# voltage_sensor_v0_3.net
KiCad netlist of a schematic drawn in EAGLE
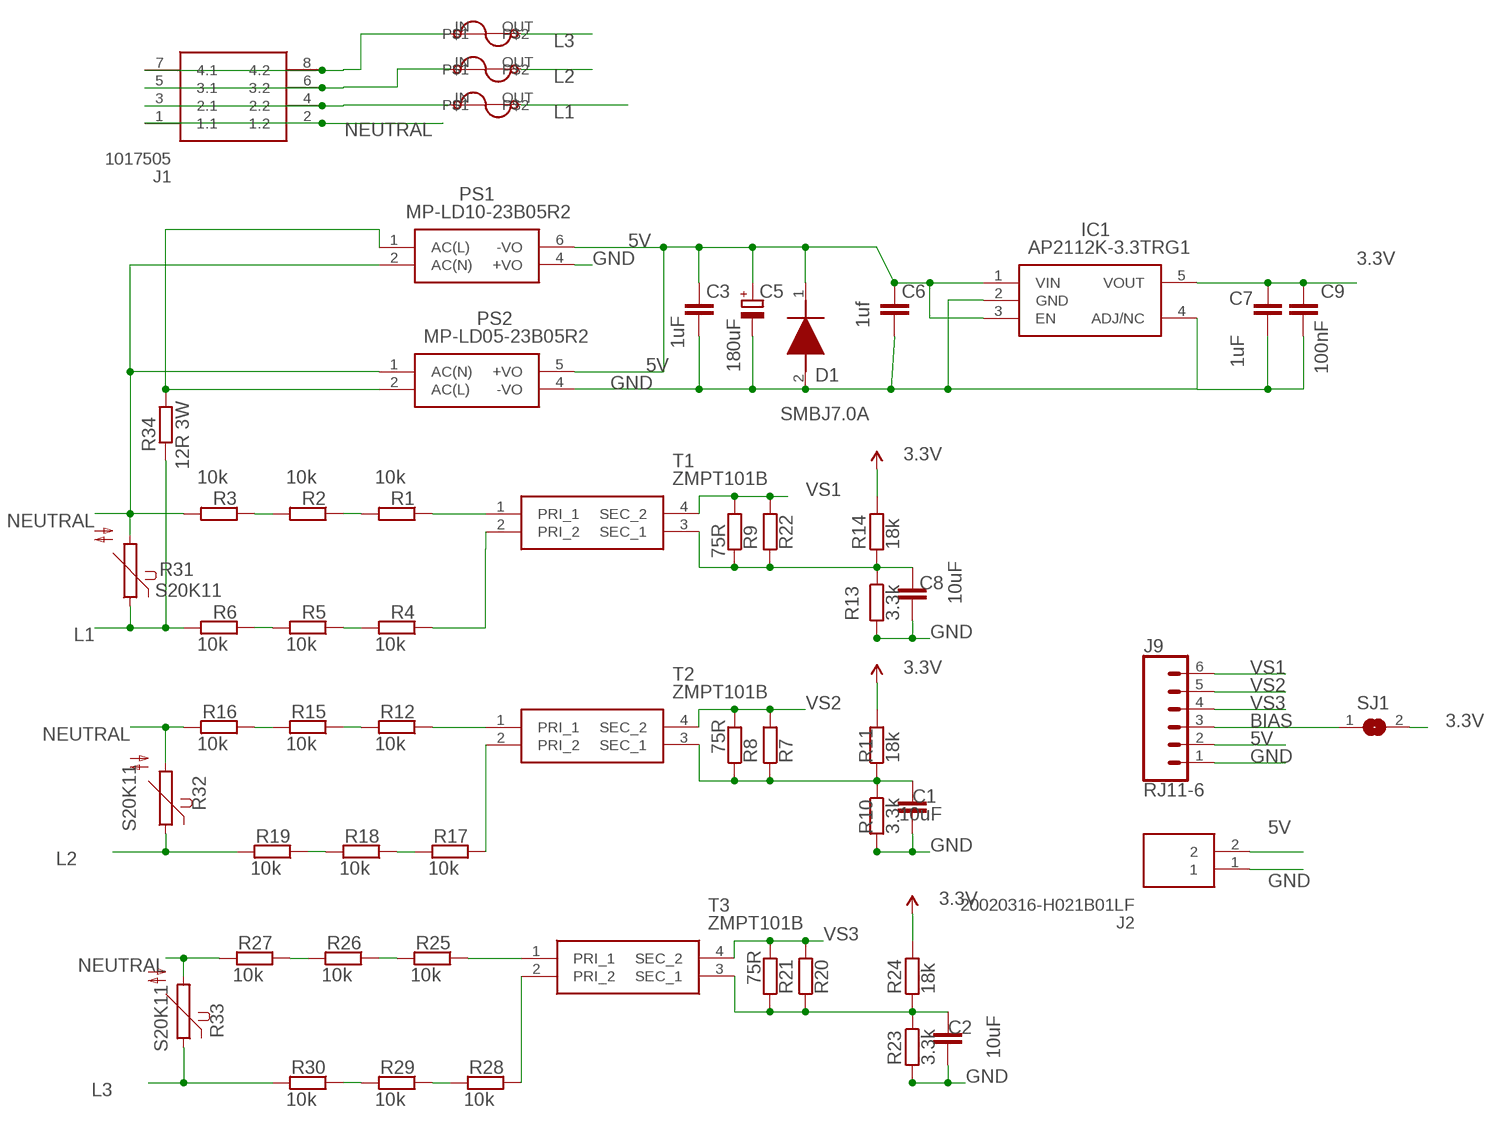
[diagram p0: schematic, sheet 1]

(export (version "E")
  (design (tool "Eeschema 10.0.6"))
  (components
    (comp (ref "C1")
      (value "10uF")
      (footprint "eagle-import:C0603")
      (libsource (lib "eagle-import") (part "C-EUC0603"))
    )
    (comp (ref "C2")
      (value "10uF")
      (footprint "eagle-import:C0603")
      (libsource (lib "eagle-import") (part "C-EUC0603"))
    )
    (comp (ref "C3")
      (value "1uF")
      (footprint "eagle-import:C0603")
      (libsource (lib "eagle-import") (part "C-EUC0603"))
    )
    (comp (ref "C5")
      (value "180uF")
      (footprint "eagle-import:PANASONIC_C")
      (libsource (lib "eagle-import") (part "CPOL-EUC"))
    )
    (comp (ref "C6")
      (value "1uf")
      (footprint "eagle-import:C0603")
      (libsource (lib "eagle-import") (part "C-EUC0603"))
    )
    (comp (ref "C7")
      (value "1uF")
      (footprint "eagle-import:C0603")
      (libsource (lib "eagle-import") (part "C-EUC0603"))
    )
    (comp (ref "C8")
      (value "10uF")
      (footprint "eagle-import:C0603")
      (libsource (lib "eagle-import") (part "C-EUC0603"))
    )
    (comp (ref "C9")
      (value "100nF")
      (footprint "eagle-import:C0603")
      (libsource (lib "eagle-import") (part "C-EUC0603"))
    )
    (comp (ref "D1")
      (value "SMBJ7.0A")
      (footprint "eagle-import:DIOM5336X244N")
      (libsource (lib "eagle-import") (part "SMBJ7.0A"))
    )
    (comp (ref "F1")
      (value "2A/250V")
      (footprint "eagle-import:BELFUSE1A")
      (libsource (lib "eagle-import") (part "BEL1AFUSE"))
    )
    (comp (ref "F2")
      (value "2A/250V")
      (footprint "eagle-import:BELFUSE1A")
      (libsource (lib "eagle-import") (part "BEL1AFUSE"))
    )
    (comp (ref "F3")
      (value "2A/250V")
      (footprint "eagle-import:BELFUSE1A")
      (libsource (lib "eagle-import") (part "BEL1AFUSE"))
    )
    (comp (ref "IC1")
      (value "AP2112K-3.3TRG1")
      (footprint "eagle-import:SOT95P282X130-5N")
      (fields (field (name "MOUSER_PART_NUMBER") "621-AP2112K-3.3TRG1"))
      (libsource (lib "eagle-import") (part "AP2112K-3.3TRG1"))
    )
    (comp (ref "J1")
      (value "1017505")
      (footprint "eagle-import:1017505")
      (fields (field (name "MOUSER_PART_NUMBER") "651-1017505"))
      (libsource (lib "eagle-import") (part "1017505"))
    )
    (comp (ref "J2")
      (value "20020316-H021B01LF")
      (footprint "eagle-import:20020316H021B01LF")
      (libsource (lib "eagle-import") (part "20020316-H021B01LF"))
    )
    (comp (ref "J9")
      (value "RJ11-6")
      (footprint "eagle-import:RJ11-6")
      (libsource (lib "eagle-import") (part "RJ11-6"))
    )
    (comp (ref "PS1")
      (value "MP-LD10-23B05R2")
      (footprint "eagle-import:MPLD1023B12R2")
      (libsource (lib "eagle-import") (part "MP-LD10-23B12R2"))
    )
    (comp (ref "PS2")
      (value "MP-LD05-23B05R2")
      (footprint "eagle-import:MPLD0523B03R2")
      (fields (field (name "MANUFACTURER_PART_NUMBER") "MP-LD05-23B03R2"))
      (libsource (lib "eagle-import") (part "MP-LD05-23B03R2"))
    )
    (comp (ref "R1")
      (value "10k")
      (footprint "eagle-import:R0603")
      (libsource (lib "eagle-import") (part "R-EU_R0603"))
    )
    (comp (ref "R2")
      (value "10k")
      (footprint "eagle-import:R0603")
      (libsource (lib "eagle-import") (part "R-EU_R0603"))
    )
    (comp (ref "R3")
      (value "10k")
      (footprint "eagle-import:R0603")
      (libsource (lib "eagle-import") (part "R-EU_R0603"))
    )
    (comp (ref "R4")
      (value "10k")
      (footprint "eagle-import:R0603")
      (libsource (lib "eagle-import") (part "R-EU_R0603"))
    )
    (comp (ref "R5")
      (value "10k")
      (footprint "eagle-import:R0603")
      (libsource (lib "eagle-import") (part "R-EU_R0603"))
    )
    (comp (ref "R6")
      (value "10k")
      (footprint "eagle-import:R0603")
      (libsource (lib "eagle-import") (part "R-EU_R0603"))
    )
    (comp (ref "R7")
      (value "R-EU_0204/7")
      (footprint "eagle-import:0204_7")
      (libsource (lib "eagle-import") (part "R-EU_0204/7"))
    )
    (comp (ref "R8")
      (value "75R")
      (footprint "eagle-import:R0603")
      (libsource (lib "eagle-import") (part "R-EU_R0603"))
    )
    (comp (ref "R9")
      (value "75R")
      (footprint "eagle-import:R0603")
      (libsource (lib "eagle-import") (part "R-EU_R0603"))
    )
    (comp (ref "R10")
      (value "3.3k")
      (footprint "eagle-import:R0603")
      (libsource (lib "eagle-import") (part "R-EU_R0603"))
    )
    (comp (ref "R11")
      (value "18k")
      (footprint "eagle-import:R0603")
      (libsource (lib "eagle-import") (part "R-EU_R0603"))
    )
    (comp (ref "R12")
      (value "10k")
      (footprint "eagle-import:R0603")
      (libsource (lib "eagle-import") (part "R-EU_R0603"))
    )
    (comp (ref "R13")
      (value "3.3k")
      (footprint "eagle-import:R0603")
      (libsource (lib "eagle-import") (part "R-EU_R0603"))
    )
    (comp (ref "R14")
      (value "18k")
      (footprint "eagle-import:R0603")
      (libsource (lib "eagle-import") (part "R-EU_R0603"))
    )
    (comp (ref "R15")
      (value "10k")
      (footprint "eagle-import:R0603")
      (libsource (lib "eagle-import") (part "R-EU_R0603"))
    )
    (comp (ref "R16")
      (value "10k")
      (footprint "eagle-import:R0603")
      (libsource (lib "eagle-import") (part "R-EU_R0603"))
    )
    (comp (ref "R17")
      (value "10k")
      (footprint "eagle-import:R0603")
      (libsource (lib "eagle-import") (part "R-EU_R0603"))
    )
    (comp (ref "R18")
      (value "10k")
      (footprint "eagle-import:R0603")
      (libsource (lib "eagle-import") (part "R-EU_R0603"))
    )
    (comp (ref "R19")
      (value "10k")
      (footprint "eagle-import:R0603")
      (libsource (lib "eagle-import") (part "R-EU_R0603"))
    )
    (comp (ref "R20")
      (value "R-EU_0204/7")
      (footprint "eagle-import:0204_7")
      (libsource (lib "eagle-import") (part "R-EU_0204/7"))
    )
    (comp (ref "R21")
      (value "75R")
      (footprint "eagle-import:R0603")
      (libsource (lib "eagle-import") (part "R-EU_R0603"))
    )
    (comp (ref "R22")
      (value "R-EU_0204/7")
      (footprint "eagle-import:0204_7")
      (libsource (lib "eagle-import") (part "R-EU_0204/7"))
    )
    (comp (ref "R23")
      (value "3.3k")
      (footprint "eagle-import:R0603")
      (libsource (lib "eagle-import") (part "R-EU_R0603"))
    )
    (comp (ref "R24")
      (value "18k")
      (footprint "eagle-import:R0603")
      (libsource (lib "eagle-import") (part "R-EU_R0603"))
    )
    (comp (ref "R25")
      (value "10k")
      (footprint "eagle-import:R0603")
      (libsource (lib "eagle-import") (part "R-EU_R0603"))
    )
    (comp (ref "R26")
      (value "10k")
      (footprint "eagle-import:R0603")
      (libsource (lib "eagle-import") (part "R-EU_R0603"))
    )
    (comp (ref "R27")
      (value "10k")
      (footprint "eagle-import:R0603")
      (libsource (lib "eagle-import") (part "R-EU_R0603"))
    )
    (comp (ref "R28")
      (value "10k")
      (footprint "eagle-import:R0603")
      (libsource (lib "eagle-import") (part "R-EU_R0603"))
    )
    (comp (ref "R29")
      (value "10k")
      (footprint "eagle-import:R0603")
      (libsource (lib "eagle-import") (part "R-EU_R0603"))
    )
    (comp (ref "R30")
      (value "10k")
      (footprint "eagle-import:R0603")
      (libsource (lib "eagle-import") (part "R-EU_R0603"))
    )
    (comp (ref "R31")
      (value "S20K11")
      (footprint "eagle-import:S20K11")
      (libsource (lib "eagle-import") (part "S20K11"))
    )
    (comp (ref "R32")
      (value "S20K11")
      (footprint "eagle-import:S20K11")
      (libsource (lib "eagle-import") (part "S20K11"))
    )
    (comp (ref "R33")
      (value "S20K11")
      (footprint "eagle-import:S20K11")
      (libsource (lib "eagle-import") (part "S20K11"))
    )
    (comp (ref "R34")
      (value "12R 3W")
      (footprint "eagle-import:R2512")
      (libsource (lib "eagle-import") (part "rcl_334_R-EU_R2512"))
    )
    (comp (ref "SJ1") (value "SJ") (footprint "eagle-import:SJ") (libsource (lib "eagle-import") (part "SJ")))
    (comp (ref "T1")
      (value "ZMPT101B")
      (footprint "eagle-import:ZMPT101B")
      (libsource (lib "eagle-import") (part "ZMPT101B"))
    )
    (comp (ref "T2")
      (value "ZMPT101B")
      (footprint "eagle-import:ZMPT101B")
      (libsource (lib "eagle-import") (part "ZMPT101B"))
    )
    (comp (ref "T3")
      (value "ZMPT101B")
      (footprint "eagle-import:ZMPT101B")
      (libsource (lib "eagle-import") (part "ZMPT101B"))
    )
  )
  (nets
    (net (code "1") (name "/5V") (class "Default")
      (node (ref "C3") (pin "1") (pinfunction "1_1") (pintype "passive"))
      (node (ref "C5") (pin "+") (pinfunction "+_+") (pintype "passive"))
      (node (ref "C6") (pin "1") (pinfunction "1_1") (pintype "passive"))
      (node (ref "D1") (pin "1") (pinfunction "K_1") (pintype "bidirectional"))
      (node (ref "IC1") (pin "1") (pinfunction "VIN_1") (pintype "bidirectional"))
      (node (ref "IC1") (pin "3") (pinfunction "EN_3") (pintype "bidirectional"))
      (node (ref "J2") (pin "2") (pinfunction "2_2") (pintype "bidirectional"))
      (node (ref "J9") (pin "2") (pinfunction "2_2") (pintype "passive"))
      (node (ref "PS1") (pin "6") (pinfunction "-VO_6") (pintype "bidirectional"))
      (node (ref "PS2") (pin "5") (pinfunction "+VO_5") (pintype "bidirectional"))
    )
    (net (code "2") (name "/BIAS") (class "Default")
      (node (ref "J9") (pin "3") (pinfunction "3_3") (pintype "passive"))
      (node (ref "SJ1") (pin "1") (pinfunction "1_1") (pintype "passive"))
    )
    (net (code "3") (name "/GND") (class "Default")
      (node (ref "C1") (pin "2") (pinfunction "2_2") (pintype "passive"))
      (node (ref "C2") (pin "2") (pinfunction "2_2") (pintype "passive"))
      (node (ref "C3") (pin "2") (pinfunction "2_2") (pintype "passive"))
      (node (ref "C5") (pin "-") (pinfunction "-_-") (pintype "passive"))
      (node (ref "C6") (pin "2") (pinfunction "2_2") (pintype "passive"))
      (node (ref "C7") (pin "2") (pinfunction "2_2") (pintype "passive"))
      (node (ref "C8") (pin "2") (pinfunction "2_2") (pintype "passive"))
      (node (ref "C9") (pin "2") (pinfunction "2_2") (pintype "passive"))
      (node (ref "D1") (pin "2") (pinfunction "A_2") (pintype "bidirectional"))
      (node (ref "IC1") (pin "2") (pinfunction "GND_2") (pintype "bidirectional"))
      (node (ref "IC1") (pin "4") (pinfunction "ADJ/NC_4") (pintype "bidirectional"))
      (node (ref "J2") (pin "1") (pinfunction "1_1") (pintype "bidirectional"))
      (node (ref "J9") (pin "1") (pinfunction "1_1") (pintype "passive"))
      (node (ref "PS1") (pin "4") (pinfunction "+VO_4") (pintype "bidirectional"))
      (node (ref "PS2") (pin "4") (pinfunction "-VO_4") (pintype "bidirectional"))
      (node (ref "R10") (pin "2") (pinfunction "2_2") (pintype "passive"))
      (node (ref "R13") (pin "2") (pinfunction "2_2") (pintype "passive"))
      (node (ref "R23") (pin "2") (pinfunction "2_2") (pintype "passive"))
    )
    (net (code "4") (name "/L1") (class "Default")
      (node (ref "F1") (pin "OUT") (pinfunction "P$1_OUT") (pintype "bidirectional"))
      (node (ref "R31") (pin "1") (pinfunction "1_1") (pintype "passive"))
      (node (ref "R34") (pin "1") (pinfunction "1_1") (pintype "passive"))
      (node (ref "R6") (pin "2") (pinfunction "2_2") (pintype "passive"))
    )
    (net (code "5") (name "/L2") (class "Default")
      (node (ref "F2") (pin "OUT") (pinfunction "P$1_OUT") (pintype "bidirectional"))
      (node (ref "R19") (pin "2") (pinfunction "2_2") (pintype "passive"))
      (node (ref "R32") (pin "1") (pinfunction "1_1") (pintype "passive"))
    )
    (net (code "6") (name "/L3") (class "Default")
      (node (ref "F3") (pin "OUT") (pinfunction "P$1_OUT") (pintype "bidirectional"))
      (node (ref "R30") (pin "2") (pinfunction "2_2") (pintype "passive"))
      (node (ref "R33") (pin "1") (pinfunction "1_1") (pintype "passive"))
    )
    (net (code "7") (name "/NEUTRAL") (class "Default")
      (node (ref "J1") (pin "1") (pinfunction "1.1_1") (pintype "bidirectional"))
      (node (ref "J1") (pin "2") (pinfunction "1.2_2") (pintype "bidirectional"))
      (node (ref "PS1") (pin "2") (pinfunction "AC(N)_2") (pintype "bidirectional"))
      (node (ref "PS2") (pin "1") (pinfunction "AC(N)_1") (pintype "bidirectional"))
      (node (ref "R16") (pin "2") (pinfunction "2_2") (pintype "passive"))
      (node (ref "R27") (pin "2") (pinfunction "2_2") (pintype "passive"))
      (node (ref "R3") (pin "2") (pinfunction "2_2") (pintype "passive"))
      (node (ref "R31") (pin "2") (pinfunction "2_2") (pintype "passive"))
      (node (ref "R32") (pin "2") (pinfunction "2_2") (pintype "passive"))
      (node (ref "R33") (pin "2") (pinfunction "2_2") (pintype "passive"))
    )
    (net (code "8") (name "/VS1") (class "Default")
      (node (ref "J9") (pin "6") (pinfunction "6_6") (pintype "passive"))
      (node (ref "R22") (pin "2") (pinfunction "2_2") (pintype "passive"))
      (node (ref "R9") (pin "2") (pinfunction "2_2") (pintype "passive"))
      (node (ref "T1") (pin "4") (pinfunction "SEC_2_4") (pintype "bidirectional"))
    )
    (net (code "9") (name "/VS2") (class "Default")
      (node (ref "J9") (pin "5") (pinfunction "5_5") (pintype "passive"))
      (node (ref "R7") (pin "2") (pinfunction "2_2") (pintype "passive"))
      (node (ref "R8") (pin "2") (pinfunction "2_2") (pintype "passive"))
      (node (ref "T2") (pin "4") (pinfunction "SEC_2_4") (pintype "bidirectional"))
    )
    (net (code "10") (name "/VS3") (class "Default")
      (node (ref "J9") (pin "4") (pinfunction "4_4") (pintype "passive"))
      (node (ref "R20") (pin "2") (pinfunction "2_2") (pintype "passive"))
      (node (ref "R21") (pin "2") (pinfunction "2_2") (pintype "passive"))
      (node (ref "T3") (pin "4") (pinfunction "SEC_2_4") (pintype "bidirectional"))
    )
    (net (code "11") (name "3.3V") (class "Default")
      (node (ref "C7") (pin "1") (pinfunction "1_1") (pintype "passive"))
      (node (ref "C9") (pin "1") (pinfunction "1_1") (pintype "passive"))
      (node (ref "IC1") (pin "5") (pinfunction "VOUT_5") (pintype "bidirectional"))
      (node (ref "R11") (pin "2") (pinfunction "2_2") (pintype "passive"))
      (node (ref "R14") (pin "2") (pinfunction "2_2") (pintype "passive"))
      (node (ref "R24") (pin "2") (pinfunction "2_2") (pintype "passive"))
      (node (ref "SJ1") (pin "2") (pinfunction "2_2") (pintype "passive"))
    )
    (net (code "12") (name "Net-(F1-P$2)") (class "Default")
      (node (ref "F1") (pin "IN") (pinfunction "P$2_IN") (pintype "bidirectional"))
      (node (ref "J1") (pin "3") (pinfunction "2.1_3") (pintype "bidirectional"))
      (node (ref "J1") (pin "4") (pinfunction "2.2_4") (pintype "bidirectional"))
    )
    (net (code "13") (name "Net-(F2-P$2)") (class "Default")
      (node (ref "F2") (pin "IN") (pinfunction "P$2_IN") (pintype "bidirectional"))
      (node (ref "J1") (pin "5") (pinfunction "3.1_5") (pintype "bidirectional"))
      (node (ref "J1") (pin "6") (pinfunction "3.2_6") (pintype "bidirectional"))
    )
    (net (code "14") (name "Net-(F3-P$2)") (class "Default")
      (node (ref "F3") (pin "IN") (pinfunction "P$2_IN") (pintype "bidirectional"))
      (node (ref "J1") (pin "7") (pinfunction "4.1_7") (pintype "bidirectional"))
      (node (ref "J1") (pin "8") (pinfunction "4.2_8") (pintype "bidirectional"))
    )
    (net (code "15") (name "Net-(PS1-AC(L))") (class "Default")
      (node (ref "PS1") (pin "1") (pinfunction "AC(L)_1") (pintype "bidirectional"))
      (node (ref "PS2") (pin "2") (pinfunction "AC(L)_2") (pintype "bidirectional"))
      (node (ref "R34") (pin "2") (pinfunction "2_2") (pintype "passive"))
    )
    (net (code "16") (name "Net-(R1-Pad2)") (class "Default")
      (node (ref "R1") (pin "2") (pinfunction "2_2") (pintype "passive"))
      (node (ref "R2") (pin "1") (pinfunction "1_1") (pintype "passive"))
    )
    (net (code "17") (name "Net-(R2-Pad2)") (class "Default")
      (node (ref "R2") (pin "2") (pinfunction "2_2") (pintype "passive"))
      (node (ref "R3") (pin "1") (pinfunction "1_1") (pintype "passive"))
    )
    (net (code "18") (name "Net-(R4-Pad2)") (class "Default")
      (node (ref "R4") (pin "2") (pinfunction "2_2") (pintype "passive"))
      (node (ref "R5") (pin "1") (pinfunction "1_1") (pintype "passive"))
    )
    (net (code "19") (name "Net-(R5-Pad2)") (class "Default")
      (node (ref "R5") (pin "2") (pinfunction "2_2") (pintype "passive"))
      (node (ref "R6") (pin "1") (pinfunction "1_1") (pintype "passive"))
    )
    (net (code "20") (name "Net-(R12-Pad2)") (class "Default")
      (node (ref "R12") (pin "2") (pinfunction "2_2") (pintype "passive"))
      (node (ref "R15") (pin "1") (pinfunction "1_1") (pintype "passive"))
    )
    (net (code "21") (name "Net-(R15-Pad2)") (class "Default")
      (node (ref "R15") (pin "2") (pinfunction "2_2") (pintype "passive"))
      (node (ref "R16") (pin "1") (pinfunction "1_1") (pintype "passive"))
    )
    (net (code "22") (name "Net-(R17-Pad2)") (class "Default")
      (node (ref "R17") (pin "2") (pinfunction "2_2") (pintype "passive"))
      (node (ref "R18") (pin "1") (pinfunction "1_1") (pintype "passive"))
    )
    (net (code "23") (name "Net-(R18-Pad2)") (class "Default")
      (node (ref "R18") (pin "2") (pinfunction "2_2") (pintype "passive"))
      (node (ref "R19") (pin "1") (pinfunction "1_1") (pintype "passive"))
    )
    (net (code "24") (name "Net-(R25-Pad2)") (class "Default")
      (node (ref "R25") (pin "2") (pinfunction "2_2") (pintype "passive"))
      (node (ref "R26") (pin "1") (pinfunction "1_1") (pintype "passive"))
    )
    (net (code "25") (name "Net-(R26-Pad2)") (class "Default")
      (node (ref "R26") (pin "2") (pinfunction "2_2") (pintype "passive"))
      (node (ref "R27") (pin "1") (pinfunction "1_1") (pintype "passive"))
    )
    (net (code "26") (name "Net-(R28-Pad2)") (class "Default")
      (node (ref "R28") (pin "2") (pinfunction "2_2") (pintype "passive"))
      (node (ref "R29") (pin "1") (pinfunction "1_1") (pintype "passive"))
    )
    (net (code "27") (name "Net-(R29-Pad2)") (class "Default")
      (node (ref "R29") (pin "2") (pinfunction "2_2") (pintype "passive"))
      (node (ref "R30") (pin "1") (pinfunction "1_1") (pintype "passive"))
    )
    (net (code "28") (name "Net-(T1-PRI_1)") (class "Default")
      (node (ref "R1") (pin "1") (pinfunction "1_1") (pintype "passive"))
      (node (ref "T1") (pin "1") (pinfunction "PRI_1_1") (pintype "bidirectional"))
    )
    (net (code "29") (name "Net-(T1-PRI_2)") (class "Default")
      (node (ref "R4") (pin "1") (pinfunction "1_1") (pintype "passive"))
      (node (ref "T1") (pin "2") (pinfunction "PRI_2_2") (pintype "bidirectional"))
    )
    (net (code "30") (name "Net-(T1-SEC_1)") (class "Default")
      (node (ref "C8") (pin "1") (pinfunction "1_1") (pintype "passive"))
      (node (ref "R13") (pin "1") (pinfunction "1_1") (pintype "passive"))
      (node (ref "R14") (pin "1") (pinfunction "1_1") (pintype "passive"))
      (node (ref "R22") (pin "1") (pinfunction "1_1") (pintype "passive"))
      (node (ref "R9") (pin "1") (pinfunction "1_1") (pintype "passive"))
      (node (ref "T1") (pin "3") (pinfunction "SEC_1_3") (pintype "bidirectional"))
    )
    (net (code "31") (name "Net-(T2-PRI_1)") (class "Default")
      (node (ref "R12") (pin "1") (pinfunction "1_1") (pintype "passive"))
      (node (ref "T2") (pin "1") (pinfunction "PRI_1_1") (pintype "bidirectional"))
    )
    (net (code "32") (name "Net-(T2-PRI_2)") (class "Default")
      (node (ref "R17") (pin "1") (pinfunction "1_1") (pintype "passive"))
      (node (ref "T2") (pin "2") (pinfunction "PRI_2_2") (pintype "bidirectional"))
    )
    (net (code "33") (name "Net-(T2-SEC_1)") (class "Default")
      (node (ref "C1") (pin "1") (pinfunction "1_1") (pintype "passive"))
      (node (ref "R10") (pin "1") (pinfunction "1_1") (pintype "passive"))
      (node (ref "R11") (pin "1") (pinfunction "1_1") (pintype "passive"))
      (node (ref "R7") (pin "1") (pinfunction "1_1") (pintype "passive"))
      (node (ref "R8") (pin "1") (pinfunction "1_1") (pintype "passive"))
      (node (ref "T2") (pin "3") (pinfunction "SEC_1_3") (pintype "bidirectional"))
    )
    (net (code "34") (name "Net-(T3-PRI_1)") (class "Default")
      (node (ref "R25") (pin "1") (pinfunction "1_1") (pintype "passive"))
      (node (ref "T3") (pin "1") (pinfunction "PRI_1_1") (pintype "bidirectional"))
    )
    (net (code "35") (name "Net-(T3-PRI_2)") (class "Default")
      (node (ref "R28") (pin "1") (pinfunction "1_1") (pintype "passive"))
      (node (ref "T3") (pin "2") (pinfunction "PRI_2_2") (pintype "bidirectional"))
    )
    (net (code "36") (name "Net-(T3-SEC_1)") (class "Default")
      (node (ref "C2") (pin "1") (pinfunction "1_1") (pintype "passive"))
      (node (ref "R20") (pin "1") (pinfunction "1_1") (pintype "passive"))
      (node (ref "R21") (pin "1") (pinfunction "1_1") (pintype "passive"))
      (node (ref "R23") (pin "1") (pinfunction "1_1") (pintype "passive"))
      (node (ref "R24") (pin "1") (pinfunction "1_1") (pintype "passive"))
      (node (ref "T3") (pin "3") (pinfunction "SEC_1_3") (pintype "bidirectional"))
    )
  )
)
